# vraimenthorspcb.net
KiCad netlist of a schematic drawn in Altium Designer
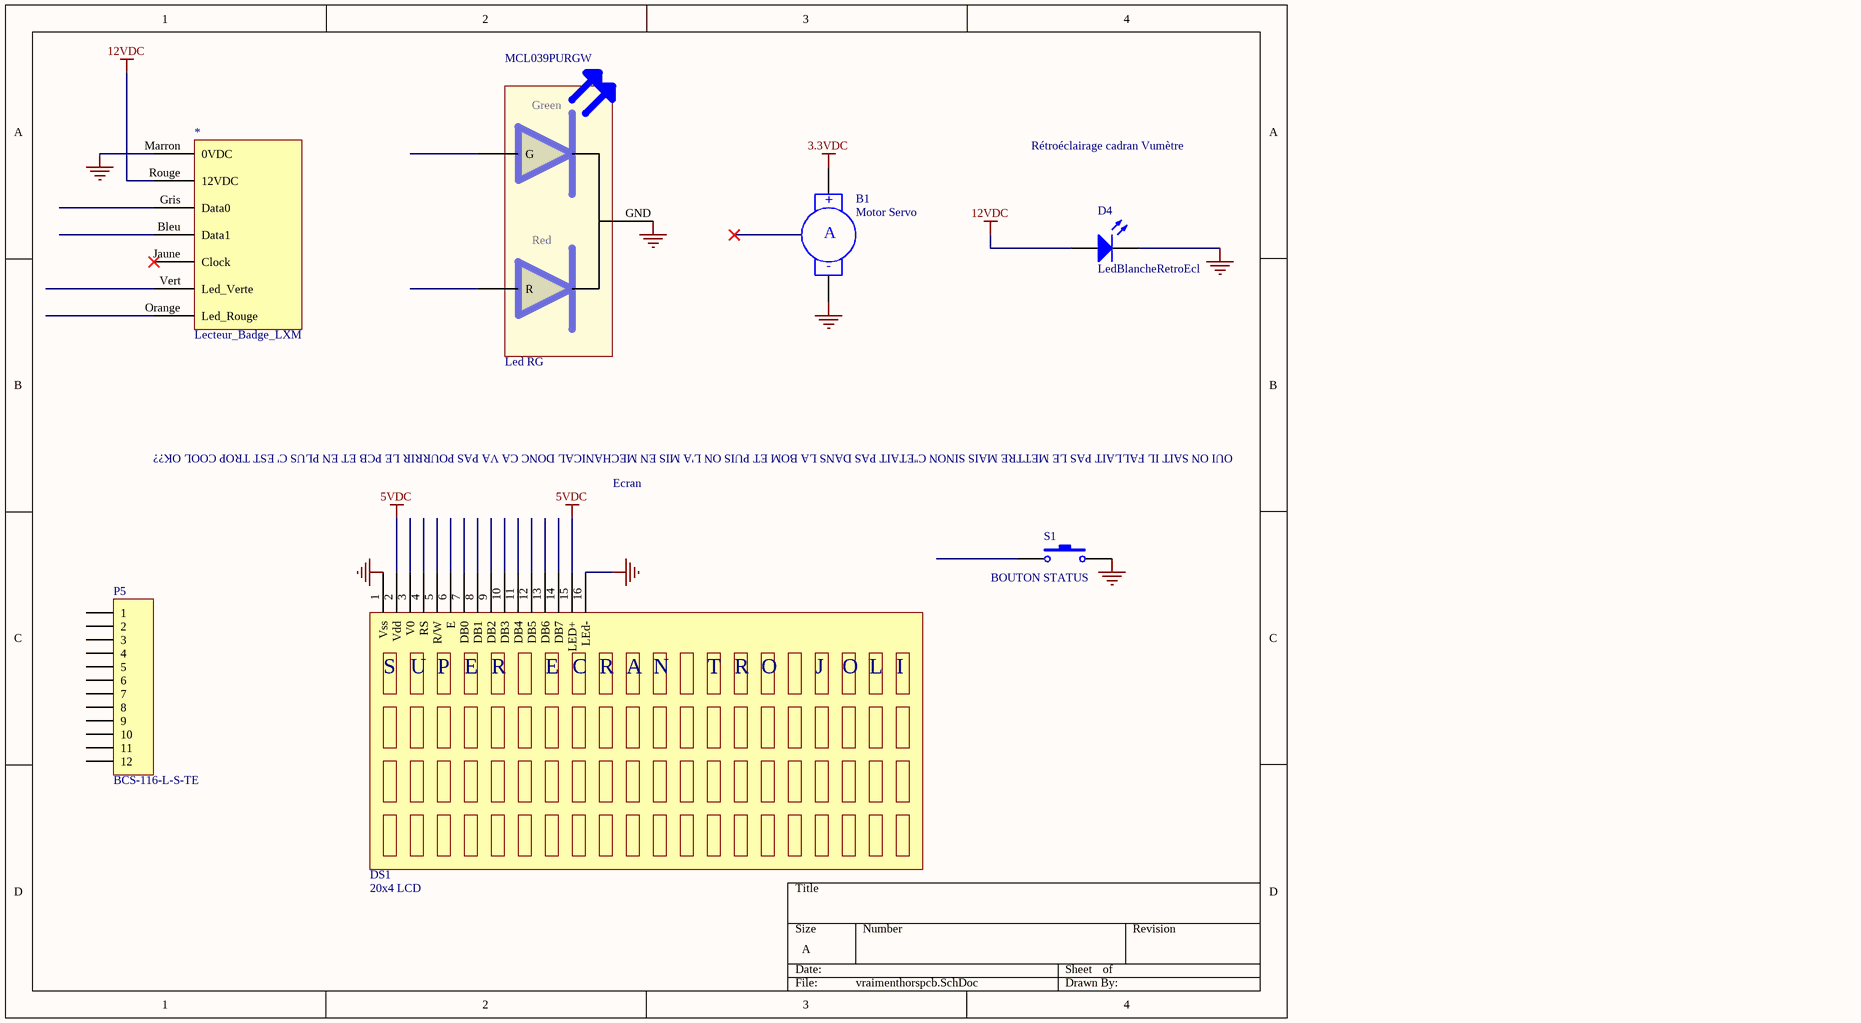
[diagram p0: vraimenthorspcb.SchDoc]

(export (version "E")
  (design (tool "Eeschema 10.0.6"))
  (components
    (comp (ref "*") (value "Lecteur_Badge_LXM") (libsource (lib "Schlib1") (part "Lecteur_Badge_LXM")))
    (comp (ref "B1")
      (value "Motor Servo")
      (footprint "RAD-0.4")
      (description "Servo Motor")
      (libsource (lib "Miscellaneous Devices") (part "Motor Servo"))
    )
    (comp (ref "D4")
      (value "LedBlancheRetroEcl")
      (footprint "LED-0")
      (description "LED Blanche retro vumetre")
      (libsource (lib "Miscellaneous Devices") (part "LED0"))
    )
    (comp (ref "DS1") (value "20x4 LCD") (libsource (lib "Schlib1") (part "MC42008A6W-FPTLW")))
    (comp (ref "MCL039PURGW") (value "Led RG") (libsource (lib "Schlib1") (part "MCL039PURGW")))
    (comp (ref "P5")
      (value "BCS-116-L-S-TE")
      (footprint "HDR1X12")
      (description "Header, 12-Pin")
      (libsource (lib "Miscellaneous Connectors") (part "Header 12"))
    )
    (comp (ref "S1")
      (value "Bouton Status")
      (footprint "SPST-2")
      (description "Switch")
      (libsource (lib "Miscellaneous Devices") (part "SW-PB"))
    )
  )
  (nets
    (net (code "1") (name "3.3VDC") (class "Default")
      (node (ref "B1") (pin "1") (pinfunction "+_1") (pintype "passive"))
    )
    (net (code "2") (name "5VDC") (class "Default")
      (node (ref "DS1") (pin "15") (pinfunction "LED+_15") (pintype "passive"))
      (node (ref "DS1") (pin "2") (pinfunction "Vdd_2") (pintype "passive"))
    )
    (net (code "3") (name "12VDC") (class "Default")
      (node (ref "*") (pin "Rouge") (pinfunction "12VDC_Rouge") (pintype "passive"))
      (node (ref "D4") (pin "1") (pinfunction "A_1") (pintype "passive"))
    )
    (net (code "4") (name "GND") (class "Default")
      (node (ref "*") (pin "Marron") (pinfunction "0VDC_Marron") (pintype "passive"))
      (node (ref "B1") (pin "2") (pinfunction "-_2") (pintype "passive"))
      (node (ref "D4") (pin "2") (pinfunction "K_2") (pintype "passive"))
      (node (ref "DS1") (pin "1") (pinfunction "Vss_1") (pintype "passive"))
      (node (ref "DS1") (pin "16") (pinfunction "LEd-_16") (pintype "passive"))
      (node (ref "MCL039PURGW") (pin "GND") (pinfunction "GND_GND") (pintype "passive"))
      (node (ref "S1") (pin "2") (pinfunction "2_2") (pintype "passive"))
    )
    (net (code "5") (name "unconnected-(*-Clock-PadJaune)") (class "Default")
      (node (ref "*") (pin "Jaune") (pinfunction "Clock_Jaune") (pintype "passive+no_connect"))
    )
    (net (code "6") (name "unconnected-(*-Data0-PadGris)") (class "Default")
      (node (ref "*") (pin "Gris") (pinfunction "Data0_Gris") (pintype "passive"))
    )
    (net (code "7") (name "unconnected-(*-Data1-PadBleu)") (class "Default")
      (node (ref "*") (pin "Bleu") (pinfunction "Data1_Bleu") (pintype "passive"))
    )
    (net (code "8") (name "unconnected-(*-Led_Rouge-PadOrange)") (class "Default")
      (node (ref "*") (pin "Orange") (pinfunction "Led_Rouge_Orange") (pintype "passive"))
    )
    (net (code "9") (name "unconnected-(*-Led_Verte-PadVert)") (class "Default")
      (node (ref "*") (pin "Vert") (pinfunction "Led_Verte_Vert") (pintype "passive"))
    )
    (net (code "10") (name "unconnected-(DS1-DB0-Pad7)") (class "Default")
      (node (ref "DS1") (pin "7") (pinfunction "DB0_7") (pintype "passive"))
    )
    (net (code "11") (name "unconnected-(DS1-DB1-Pad8)") (class "Default")
      (node (ref "DS1") (pin "8") (pinfunction "DB1_8") (pintype "passive"))
    )
    (net (code "12") (name "unconnected-(DS1-DB2-Pad9)") (class "Default")
      (node (ref "DS1") (pin "9") (pinfunction "DB2_9") (pintype "passive"))
    )
    (net (code "13") (name "unconnected-(DS1-DB3-Pad10)") (class "Default")
      (node (ref "DS1") (pin "10") (pinfunction "DB3_10") (pintype "passive"))
    )
    (net (code "14") (name "unconnected-(DS1-DB4-Pad11)") (class "Default")
      (node (ref "DS1") (pin "11") (pinfunction "DB4_11") (pintype "passive"))
    )
    (net (code "15") (name "unconnected-(DS1-DB5-Pad12)") (class "Default")
      (node (ref "DS1") (pin "12") (pinfunction "DB5_12") (pintype "passive"))
    )
    (net (code "16") (name "unconnected-(DS1-DB6-Pad13)") (class "Default")
      (node (ref "DS1") (pin "13") (pinfunction "DB6_13") (pintype "passive"))
    )
    (net (code "17") (name "unconnected-(DS1-DB7-Pad14)") (class "Default")
      (node (ref "DS1") (pin "14") (pinfunction "DB7_14") (pintype "passive"))
    )
    (net (code "18") (name "unconnected-(DS1-E-Pad6)") (class "Default")
      (node (ref "DS1") (pin "6") (pinfunction "E_6") (pintype "passive"))
    )
    (net (code "19") (name "unconnected-(DS1-RS-Pad4)") (class "Default")
      (node (ref "DS1") (pin "4") (pinfunction "RS_4") (pintype "passive"))
    )
    (net (code "20") (name "unconnected-(DS1-R{slash}W-Pad5)") (class "Default")
      (node (ref "DS1") (pin "5") (pinfunction "R/W_5") (pintype "passive"))
    )
    (net (code "21") (name "unconnected-(DS1-V0-Pad3)") (class "Default")
      (node (ref "DS1") (pin "3") (pinfunction "V0_3") (pintype "passive"))
    )
    (net (code "22") (name "unconnected-(MCL039PURGW-PadG)") (class "Default")
      (node (ref "MCL039PURGW") (pin "G") (pinfunction "G_G") (pintype "passive"))
    )
    (net (code "23") (name "unconnected-(MCL039PURGW-PadR)") (class "Default")
      (node (ref "MCL039PURGW") (pin "R") (pinfunction "R_R") (pintype "passive"))
    )
    (net (code "24") (name "unconnected-(P5-Pad1)") (class "Default")
      (node (ref "P5") (pin "1") (pinfunction "1_1") (pintype "passive"))
    )
    (net (code "25") (name "unconnected-(P5-Pad2)") (class "Default")
      (node (ref "P5") (pin "2") (pinfunction "2_2") (pintype "passive"))
    )
    (net (code "26") (name "unconnected-(P5-Pad3)") (class "Default")
      (node (ref "P5") (pin "3") (pinfunction "3_3") (pintype "passive"))
    )
    (net (code "27") (name "unconnected-(P5-Pad4)") (class "Default")
      (node (ref "P5") (pin "4") (pinfunction "4_4") (pintype "passive"))
    )
    (net (code "28") (name "unconnected-(P5-Pad5)") (class "Default")
      (node (ref "P5") (pin "5") (pinfunction "5_5") (pintype "passive"))
    )
    (net (code "29") (name "unconnected-(P5-Pad6)") (class "Default")
      (node (ref "P5") (pin "6") (pinfunction "6_6") (pintype "passive"))
    )
    (net (code "30") (name "unconnected-(P5-Pad7)") (class "Default")
      (node (ref "P5") (pin "7") (pinfunction "7_7") (pintype "passive"))
    )
    (net (code "31") (name "unconnected-(P5-Pad8)") (class "Default")
      (node (ref "P5") (pin "8") (pinfunction "8_8") (pintype "passive"))
    )
    (net (code "32") (name "unconnected-(P5-Pad9)") (class "Default")
      (node (ref "P5") (pin "9") (pinfunction "9_9") (pintype "passive"))
    )
    (net (code "33") (name "unconnected-(P5-Pad10)") (class "Default")
      (node (ref "P5") (pin "10") (pinfunction "10_10") (pintype "passive"))
    )
    (net (code "34") (name "unconnected-(P5-Pad11)") (class "Default")
      (node (ref "P5") (pin "11") (pinfunction "11_11") (pintype "passive"))
    )
    (net (code "35") (name "unconnected-(P5-Pad12)") (class "Default")
      (node (ref "P5") (pin "12") (pinfunction "12_12") (pintype "passive"))
    )
    (net (code "36") (name "unconnected-(S1-Pad1)") (class "Default")
      (node (ref "S1") (pin "1") (pinfunction "1_1") (pintype "passive"))
    )
  )
)
